# TSC_Project_v29.net
KiCad netlist of a schematic drawn in EAGLE
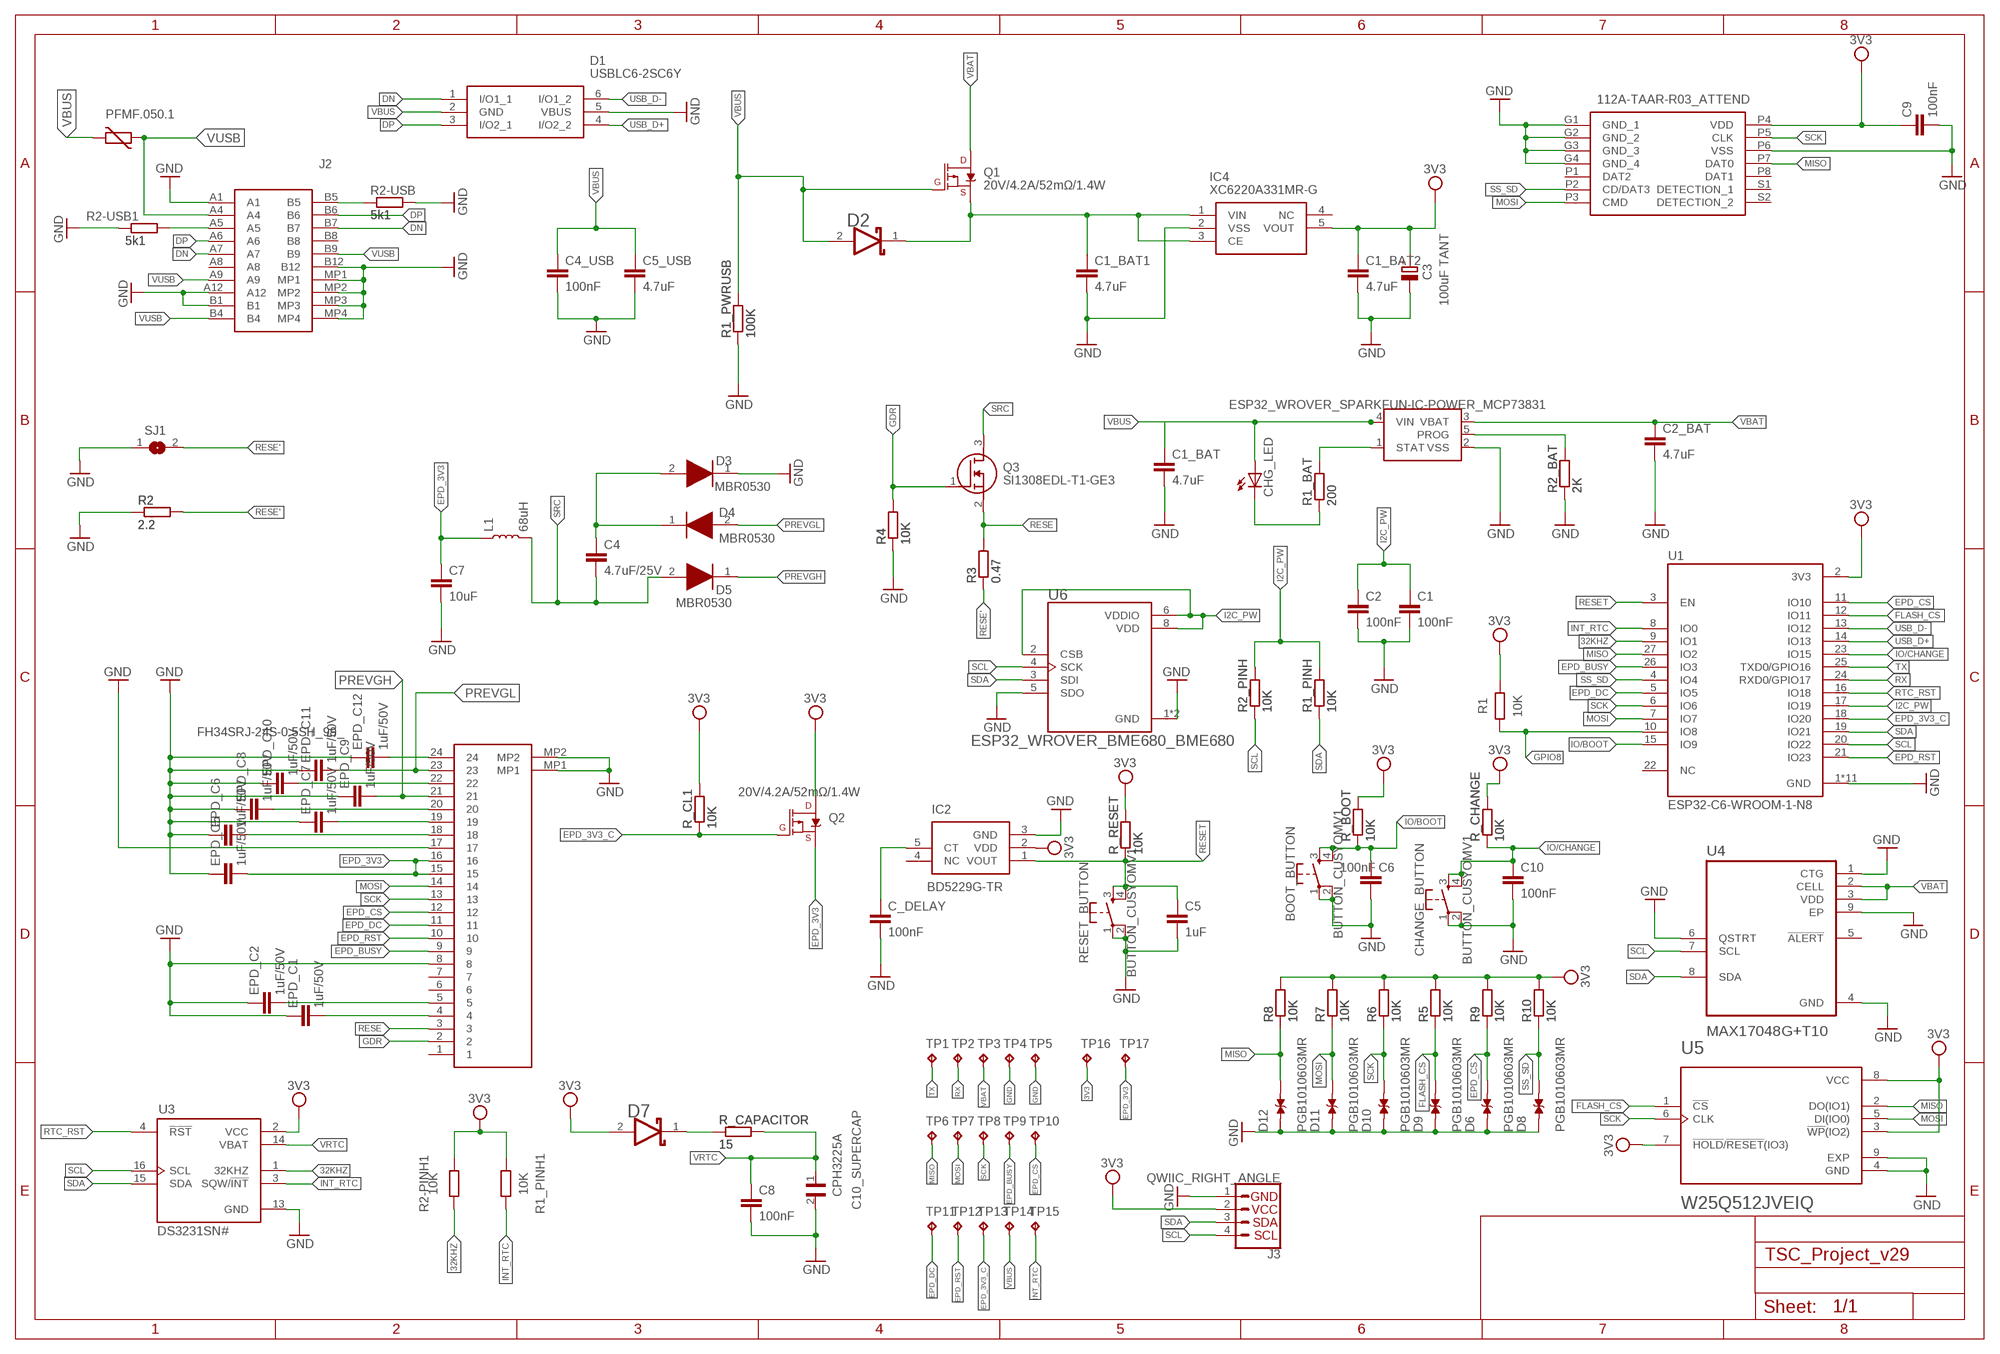
[diagram p0: schematic, sheet 1]

(export (version "E")
  (design (tool "Eeschema 10.0.6"))
  (components
    (comp (ref "BOOT_BUTTON")
      (value "BUTTON_CUSYOMV1")
      (footprint "eagle-import:MYBUTTON")
      (libsource (lib "eagle-import") (part "BUTTON_CUSYOMV1"))
    )
    (comp (ref "C1")
      (value "100nF")
      (footprint "eagle-import:ESP32_WROVER_EAGLE-LTSPICE_C0402")
      (libsource (lib "eagle-import") (part "ESP32_WROVER_EAGLE-LTSPICE_CC0402"))
    )
    (comp (ref "C1_BAT")
      (value "4.7uF")
      (footprint "eagle-import:ESP32_WROVER_EAGLE-LTSPICE_C0402")
      (libsource (lib "eagle-import") (part "ESP32_WROVER_EAGLE-LTSPICE_CC0402"))
    )
    (comp (ref "C1_BAT1")
      (value "4.7uF")
      (footprint "eagle-import:ESP32_WROVER_EAGLE-LTSPICE_C0402")
      (libsource (lib "eagle-import") (part "EAGLE-LTSPICE_CC0402"))
    )
    (comp (ref "C1_BAT2")
      (value "4.7uF")
      (footprint "eagle-import:ESP32_WROVER_EAGLE-LTSPICE_C0402")
      (libsource (lib "eagle-import") (part "EAGLE-LTSPICE_CC0402"))
    )
    (comp (ref "C2")
      (value "100nF")
      (footprint "eagle-import:ESP32_WROVER_EAGLE-LTSPICE_C0402")
      (libsource (lib "eagle-import") (part "ESP32_WROVER_EAGLE-LTSPICE_CC0402"))
    )
    (comp (ref "C2_BAT")
      (value "4.7uF")
      (footprint "eagle-import:ESP32_WROVER_EAGLE-LTSPICE_C0402")
      (libsource (lib "eagle-import") (part "ESP32_WROVER_EAGLE-LTSPICE_CC0402"))
    )
    (comp (ref "C3")
      (value "100uF TANT")
      (footprint "eagle-import:RCL_CT3528")
      (libsource (lib "eagle-import") (part "RCL_CPOL-EUCT3528"))
    )
    (comp (ref "C4")
      (value "4.7uF/25V")
      (footprint "eagle-import:ESP32_WROVER_EAGLE-LTSPICE_C0402")
      (libsource (lib "eagle-import") (part "ESP32_WROVER_EAGLE-LTSPICE_CC0402"))
    )
    (comp (ref "C4_USB")
      (value "100nF")
      (footprint "eagle-import:ESP32_WROVER_EAGLE-LTSPICE_C0402")
      (libsource (lib "eagle-import") (part "EAGLE-LTSPICE_CC0402"))
    )
    (comp (ref "C5")
      (value "1uF")
      (footprint "eagle-import:ESP32_WROVER_EAGLE-LTSPICE_C0402")
      (libsource (lib "eagle-import") (part "ESP32_WROVER_EAGLE-LTSPICE_CC0402"))
    )
    (comp (ref "C5_USB")
      (value "4.7uF")
      (footprint "eagle-import:ESP32_WROVER_EAGLE-LTSPICE_C0402")
      (libsource (lib "eagle-import") (part "EAGLE-LTSPICE_CC0402"))
    )
    (comp (ref "C6")
      (value "100nF")
      (footprint "eagle-import:ESP32_WROVER_EAGLE-LTSPICE_C0402")
      (libsource (lib "eagle-import") (part "ESP32_WROVER_EAGLE-LTSPICE_CC0402"))
    )
    (comp (ref "C7")
      (value "10uF")
      (footprint "eagle-import:ESP32_WROVER_EAGLE-LTSPICE_C0402")
      (libsource (lib "eagle-import") (part "ESP32_WROVER_EAGLE-LTSPICE_CC0402"))
    )
    (comp (ref "C8")
      (value "100nF")
      (footprint "eagle-import:ESP32_WROVER_EAGLE-LTSPICE_C0402")
      (libsource (lib "eagle-import") (part "ESP32_WROVER_EAGLE-LTSPICE_CC0402"))
    )
    (comp (ref "C9")
      (value "100nF")
      (footprint "eagle-import:ESP32_WROVER_EAGLE-LTSPICE_C0402")
      (libsource (lib "eagle-import") (part "ESP32_WROVER_EAGLE-LTSPICE_CC0402"))
    )
    (comp (ref "C10")
      (value "100nF")
      (footprint "eagle-import:ESP32_WROVER_EAGLE-LTSPICE_C0402")
      (libsource (lib "eagle-import") (part "ESP32_WROVER_EAGLE-LTSPICE_CC0402"))
    )
    (comp (ref "C10_SUPERCAP")
      (value "CPH3225A")
      (footprint "eagle-import:CAPCP3225X100N")
      (fields (field (name "MF") "Seiko Instruments"))
      (libsource (lib "eagle-import") (part "CPH3225A"))
    )
    (comp (ref "CHANGE_BUTTON")
      (value "BUTTON_CUSYOMV1")
      (footprint "eagle-import:MYBUTTON")
      (libsource (lib "eagle-import") (part "BUTTON_CUSYOMV1"))
    )
    (comp (ref "CHG_LED")
      (value "ADAFRUIT_LEDCHIP-LED0603")
      (footprint "eagle-import:ADAFRUIT_CHIP-LED0603")
      (libsource (lib "eagle-import") (part "ADAFRUIT_LEDCHIP-LED0603"))
    )
    (comp (ref "C_DELAY")
      (value "100nF")
      (footprint "eagle-import:ESP32_WROVER_EAGLE-LTSPICE_C0402")
      (libsource (lib "eagle-import") (part "EAGLE-LTSPICE_CC0402"))
    )
    (comp (ref "D1")
      (value "USBLC6-2SC6Y")
      (footprint "eagle-import:SOT95P280X145-6N")
      (fields (field (name "MF") "STMicroelectronics"))
      (libsource (lib "eagle-import") (part "USBLC6-2SC6Y"))
    )
    (comp (ref "D2")
      (value "ESP32_WROVER_AVX---SD0805S020S1R0_AVX_SD0805S020S1R0_0_0AVX_SD0805S020S1R0_0_0")
      (footprint "eagle-import:ESP32_WROVER_AVX---SD0805S020S1R0_AVX_SD0805S020S1R0_0")
      (fields
        (field (name "DIGIKEY_PART_NUMBER") "478-7800-1-ND")
        (field (name "MF") "AVX")
        (field (name "MOUSER_PART_NUMBER") "581-SD0805S020S1R0")
      )
      (libsource (lib "eagle-import") (part "ESP32_WROVER_AVX---SD0805S020S1R0_AVX_SD0805S020S1R0_0_0AVX_SD0805S020S1R0_0_0"))
    )
    (comp (ref "D3")
      (value "MBR0530")
      (footprint "eagle-import:SOD3716X135N")
      (fields (field (name "MF") "ON Semiconductor"))
      (libsource (lib "eagle-import") (part "MBR0530"))
    )
    (comp (ref "D4")
      (value "MBR0530")
      (footprint "eagle-import:SOD3716X135N")
      (fields (field (name "MF") "ON Semiconductor"))
      (libsource (lib "eagle-import") (part "MBR0530"))
    )
    (comp (ref "D5")
      (value "MBR0530")
      (footprint "eagle-import:SOD3716X135N")
      (fields (field (name "MF") "ON Semiconductor"))
      (libsource (lib "eagle-import") (part "MBR0530"))
    )
    (comp (ref "D6")
      (value "PGB1010603MR")
      (footprint "eagle-import:DIOC1608X36N")
      (fields (field (name "MF") "Littelfuse Inc."))
      (libsource (lib "eagle-import") (part "PGB1010603MR"))
    )
    (comp (ref "D7")
      (value "ESP32_WROVER_AVX---SD0805S020S1R0_AVX_SD0805S020S1R0_0_0AVX_SD0805S020S1R0_0_0")
      (footprint "eagle-import:ESP32_WROVER_AVX---SD0805S020S1R0_AVX_SD0805S020S1R0_0")
      (fields
        (field (name "DIGIKEY_PART_NUMBER") "478-7800-1-ND")
        (field (name "MF") "AVX")
        (field (name "MOUSER_PART_NUMBER") "581-SD0805S020S1R0")
      )
      (libsource (lib "eagle-import") (part "ESP32_WROVER_AVX---SD0805S020S1R0_AVX_SD0805S020S1R0_0_0AVX_SD0805S020S1R0_0_0"))
    )
    (comp (ref "D8")
      (value "PGB1010603MR")
      (footprint "eagle-import:DIOC1608X36N")
      (fields (field (name "MF") "Littelfuse Inc."))
      (libsource (lib "eagle-import") (part "PGB1010603MR"))
    )
    (comp (ref "D9")
      (value "PGB1010603MR")
      (footprint "eagle-import:DIOC1608X36N")
      (fields (field (name "MF") "Littelfuse Inc."))
      (libsource (lib "eagle-import") (part "PGB1010603MR"))
    )
    (comp (ref "D10")
      (value "PGB1010603MR")
      (footprint "eagle-import:DIOC1608X36N")
      (fields (field (name "MF") "Littelfuse Inc."))
      (libsource (lib "eagle-import") (part "PGB1010603MR"))
    )
    (comp (ref "D11")
      (value "PGB1010603MR")
      (footprint "eagle-import:DIOC1608X36N")
      (fields (field (name "MF") "Littelfuse Inc."))
      (libsource (lib "eagle-import") (part "PGB1010603MR"))
    )
    (comp (ref "D12")
      (value "PGB1010603MR")
      (footprint "eagle-import:DIOC1608X36N")
      (fields (field (name "MF") "Littelfuse Inc."))
      (libsource (lib "eagle-import") (part "PGB1010603MR"))
    )
    (comp (ref "EPD_C1")
      (value "1uF/50V")
      (footprint "eagle-import:ESP32_WROVER_EAGLE-LTSPICE_C0402")
      (libsource (lib "eagle-import") (part "ESP32_WROVER_EAGLE-LTSPICE_CC0402"))
    )
    (comp (ref "EPD_C2")
      (value "1uF/50V")
      (footprint "eagle-import:ESP32_WROVER_EAGLE-LTSPICE_C0402")
      (libsource (lib "eagle-import") (part "ESP32_WROVER_EAGLE-LTSPICE_CC0402"))
    )
    (comp (ref "EPD_C5")
      (value "1uF/50V")
      (footprint "eagle-import:ESP32_WROVER_EAGLE-LTSPICE_C0402")
      (libsource (lib "eagle-import") (part "ESP32_WROVER_EAGLE-LTSPICE_CC0402"))
    )
    (comp (ref "EPD_C6")
      (value "1uF/50V")
      (footprint "eagle-import:ESP32_WROVER_EAGLE-LTSPICE_C0402")
      (libsource (lib "eagle-import") (part "ESP32_WROVER_EAGLE-LTSPICE_CC0402"))
    )
    (comp (ref "EPD_C7")
      (value "1uF/50V")
      (footprint "eagle-import:ESP32_WROVER_EAGLE-LTSPICE_C0402")
      (libsource (lib "eagle-import") (part "ESP32_WROVER_EAGLE-LTSPICE_CC0402"))
    )
    (comp (ref "EPD_C8")
      (value "1uF/50V")
      (footprint "eagle-import:ESP32_WROVER_EAGLE-LTSPICE_C0402")
      (libsource (lib "eagle-import") (part "ESP32_WROVER_EAGLE-LTSPICE_CC0402"))
    )
    (comp (ref "EPD_C9")
      (value "1uF/50V")
      (footprint "eagle-import:ESP32_WROVER_EAGLE-LTSPICE_C0402")
      (libsource (lib "eagle-import") (part "ESP32_WROVER_EAGLE-LTSPICE_CC0402"))
    )
    (comp (ref "EPD_C10")
      (value "1uF/50V")
      (footprint "eagle-import:ESP32_WROVER_EAGLE-LTSPICE_C0402")
      (libsource (lib "eagle-import") (part "ESP32_WROVER_EAGLE-LTSPICE_CC0402"))
    )
    (comp (ref "EPD_C11")
      (value "1uF/50V")
      (footprint "eagle-import:ESP32_WROVER_EAGLE-LTSPICE_C0402")
      (libsource (lib "eagle-import") (part "ESP32_WROVER_EAGLE-LTSPICE_CC0402"))
    )
    (comp (ref "EPD_C12")
      (value "1uF/50V")
      (footprint "eagle-import:ESP32_WROVER_EAGLE-LTSPICE_C0402")
      (libsource (lib "eagle-import") (part "ESP32_WROVER_EAGLE-LTSPICE_CC0402"))
    )
    (comp (ref "IC2")
      (value "BD5229G-TR")
      (footprint "eagle-import:SOT95P280X125-5N")
      (fields (field (name "MOUSER_PART_NUMBER") "755-BD5229G-TR"))
      (libsource (lib "eagle-import") (part "BD5229G-TR"))
    )
    (comp (ref "IC4")
      (value "XC6220A331MR-G")
      (footprint "eagle-import:SOT95P280X120-5N")
      (fields (field (name "MOUSER_PART_NUMBER") "865-XC6220A331MR-G"))
      (libsource (lib "eagle-import") (part "XC6220A331MR-G"))
    )
    (comp (ref "J1")
      (value "FH34SRJ-24S-0.5SH_99_")
      (footprint "eagle-import:FH34SRJ24S05SH99")
      (fields
        (field (name "MANUFACTURER_PART_NUMBER") "FH34SRJ-24S-0.5SH(99)")
        (field (name "MOUSER_PART_NUMBER") "798-FH34SRJ24S05SH99")
      )
      (libsource (lib "eagle-import") (part "FH34SRJ-24S-0.5SH_99_"))
    )
    (comp (ref "J2")
      (value "SAMACSYS_PARTS_USB4110-GF-A")
      (footprint "eagle-import:SAMACSYS_PARTS_USB4110GFA")
      (fields
        (field (name "MANUFACTURER_PART_NUMBER") "USB4110-GF-A")
        (field (name "MOUSER_PART_NUMBER") "640-USB4110-GF-A")
      )
      (libsource (lib "eagle-import") (part "SAMACSYS_PARTS_USB4110-GF-A"))
    )
    (comp (ref "J3")
      (value "QWIIC_RIGHT_ANGLE")
      (footprint "eagle-import:JST04_1MM_RA")
      (libsource (lib "eagle-import") (part "QWIIC_CONNECTORJS-1MM"))
    )
    (comp (ref "J4")
      (value "112A-TAAR-R03_ATTEND")
      (footprint "eagle-import:112ATAARR03ATTEND")
      (fields (field (name "MANUFACTURER_PART_NUMBER") "112A-TAAR-R03 ATTEND"))
      (libsource (lib "eagle-import") (part "112A-TAAR-R03_ATTEND"))
    )
    (comp (ref "L1")
      (value "68uH")
      (footprint "eagle-import:CR75")
      (libsource (lib "eagle-import") (part "INDUCTOR-CR75-68UH"))
    )
    (comp (ref "PFMF.050.1")
      (value "ESP32C6_VARISTORCN1812")
      (footprint "eagle-import:ESP32C6_VARISTOR_CT_CN1812")
      (libsource (lib "eagle-import") (part "ESP32C6_VARISTORCN1812"))
    )
    (comp (ref "Q1")
      (value "20V/4.2A/52mΩ/1.4W")
      (footprint "eagle-import:ESP32_WROVER_SPARKFUN-DISCRETESEMI_SOT23-3")
      (libsource (lib "eagle-import") (part "ESP32_WROVER_SPARKFUN-DISCRETESEMI_MOSFET_PCH-DMG2305UX-7"))
    )
    (comp (ref "Q2")
      (value "20V/4.2A/52mΩ/1.4W")
      (footprint "eagle-import:ESP32_WROVER_SPARKFUN-DISCRETESEMI_SOT23-3")
      (libsource (lib "eagle-import") (part "ESP32_WROVER_SPARKFUN-DISCRETESEMI_MOSFET_PCH-DMG2305UX-7"))
    )
    (comp (ref "Q3")
      (value "SI1308EDL-T1-GE3")
      (footprint "eagle-import:SOT65P210X110-3N")
      (fields (field (name "MF") "Vishay Siliconix"))
      (libsource (lib "eagle-import") (part "SI1308EDL-T1-GE3"))
    )
    (comp (ref "R1")
      (value "10K")
      (footprint "eagle-import:ESP32_WROVER_EAGLE-LTSPICE_R0402")
      (libsource (lib "eagle-import") (part "ESP32_WROVER_EAGLE-LTSPICE_RR0402"))
    )
    (comp (ref "R1_BAT")
      (value "200")
      (footprint "eagle-import:ESP32_WROVER_EAGLE-LTSPICE_R0402")
      (libsource (lib "eagle-import") (part "ESP32_WROVER_EAGLE-LTSPICE_RR0402"))
    )
    (comp (ref "R1_PINH")
      (value "10K")
      (footprint "eagle-import:ESP32_WROVER_EAGLE-LTSPICE_R0402")
      (libsource (lib "eagle-import") (part "ESP32_WROVER_EAGLE-LTSPICE_RR0402"))
    )
    (comp (ref "R1_PINH1")
      (value "10K")
      (footprint "eagle-import:ESP32_WROVER_EAGLE-LTSPICE_R0402")
      (libsource (lib "eagle-import") (part "ESP32_WROVER_EAGLE-LTSPICE_RR0402"))
    )
    (comp (ref "R1_PWRUSB")
      (value "100K")
      (footprint "eagle-import:ESP32_WROVER_EAGLE-LTSPICE_R0402")
      (libsource (lib "eagle-import") (part "ESP32_WROVER_EAGLE-LTSPICE_RR0402"))
    )
    (comp (ref "R2")
      (value "2.2")
      (footprint "eagle-import:ESP32_WROVER_EAGLE-LTSPICE_R0402")
      (libsource (lib "eagle-import") (part "ESP32_WROVER_EAGLE-LTSPICE_RR0402"))
    )
    (comp (ref "R2-PINH1")
      (value "10K")
      (footprint "eagle-import:ESP32_WROVER_EAGLE-LTSPICE_R0402")
      (libsource (lib "eagle-import") (part "ESP32_WROVER_EAGLE-LTSPICE_RR0402"))
    )
    (comp (ref "R2-USB")
      (value "5k1")
      (footprint "eagle-import:ESP32_WROVER_EAGLE-LTSPICE_R0402")
      (libsource (lib "eagle-import") (part "ESP32_WROVER_EAGLE-LTSPICE_RR0402"))
    )
    (comp (ref "R2-USB1")
      (value "5k1")
      (footprint "eagle-import:ESP32_WROVER_EAGLE-LTSPICE_R0402")
      (libsource (lib "eagle-import") (part "ESP32_WROVER_EAGLE-LTSPICE_RR0402"))
    )
    (comp (ref "R2_BAT")
      (value "2K")
      (footprint "eagle-import:ESP32_WROVER_EAGLE-LTSPICE_R0402")
      (libsource (lib "eagle-import") (part "ESP32_WROVER_EAGLE-LTSPICE_RR0402"))
    )
    (comp (ref "R2_PINH")
      (value "10K")
      (footprint "eagle-import:ESP32_WROVER_EAGLE-LTSPICE_R0402")
      (libsource (lib "eagle-import") (part "ESP32_WROVER_EAGLE-LTSPICE_RR0402"))
    )
    (comp (ref "R3")
      (value "0.47")
      (footprint "eagle-import:ESP32_WROVER_EAGLE-LTSPICE_R0402")
      (libsource (lib "eagle-import") (part "ESP32_WROVER_EAGLE-LTSPICE_RR0402"))
    )
    (comp (ref "R4")
      (value "10K")
      (footprint "eagle-import:ESP32_WROVER_EAGLE-LTSPICE_R0402")
      (libsource (lib "eagle-import") (part "ESP32_WROVER_EAGLE-LTSPICE_RR0402"))
    )
    (comp (ref "R5")
      (value "10K")
      (footprint "eagle-import:ESP32_WROVER_EAGLE-LTSPICE_R0402")
      (libsource (lib "eagle-import") (part "ESP32_WROVER_EAGLE-LTSPICE_RR0402"))
    )
    (comp (ref "R6")
      (value "10K")
      (footprint "eagle-import:ESP32_WROVER_EAGLE-LTSPICE_R0402")
      (libsource (lib "eagle-import") (part "ESP32_WROVER_EAGLE-LTSPICE_RR0402"))
    )
    (comp (ref "R7")
      (value "10K")
      (footprint "eagle-import:ESP32_WROVER_EAGLE-LTSPICE_R0402")
      (libsource (lib "eagle-import") (part "ESP32_WROVER_EAGLE-LTSPICE_RR0402"))
    )
    (comp (ref "R8")
      (value "10K")
      (footprint "eagle-import:ESP32_WROVER_EAGLE-LTSPICE_R0402")
      (libsource (lib "eagle-import") (part "ESP32_WROVER_EAGLE-LTSPICE_RR0402"))
    )
    (comp (ref "R9")
      (value "10K")
      (footprint "eagle-import:ESP32_WROVER_EAGLE-LTSPICE_R0402")
      (libsource (lib "eagle-import") (part "ESP32_WROVER_EAGLE-LTSPICE_RR0402"))
    )
    (comp (ref "R10")
      (value "10K")
      (footprint "eagle-import:ESP32_WROVER_EAGLE-LTSPICE_R0402")
      (libsource (lib "eagle-import") (part "ESP32_WROVER_EAGLE-LTSPICE_RR0402"))
    )
    (comp (ref "RESET_BUTTON")
      (value "BUTTON_CUSYOMV1")
      (footprint "eagle-import:MYBUTTON")
      (libsource (lib "eagle-import") (part "BUTTON_CUSYOMV1"))
    )
    (comp (ref "R_BOOT")
      (value "10K")
      (footprint "eagle-import:ESP32_WROVER_EAGLE-LTSPICE_R0402")
      (libsource (lib "eagle-import") (part "ESP32_WROVER_EAGLE-LTSPICE_RR0402"))
    )
    (comp (ref "R_CAPACITOR")
      (value "15")
      (footprint "eagle-import:ESP32_WROVER_EAGLE-LTSPICE_R0402")
      (libsource (lib "eagle-import") (part "ESP32_WROVER_EAGLE-LTSPICE_RR0402"))
    )
    (comp (ref "R_CHANGE")
      (value "10K")
      (footprint "eagle-import:ESP32_WROVER_EAGLE-LTSPICE_R0402")
      (libsource (lib "eagle-import") (part "ESP32_WROVER_EAGLE-LTSPICE_RR0402"))
    )
    (comp (ref "R_CL1")
      (value "10K")
      (footprint "eagle-import:ESP32_WROVER_EAGLE-LTSPICE_R0402")
      (libsource (lib "eagle-import") (part "ESP32_WROVER_EAGLE-LTSPICE_RR0402"))
    )
    (comp (ref "R_RESET")
      (value "10K")
      (footprint "eagle-import:ESP32_WROVER_EAGLE-LTSPICE_R0402")
      (libsource (lib "eagle-import") (part "ESP32_WROVER_EAGLE-LTSPICE_RR0402"))
    )
    (comp (ref "SJ1") (value "SJ") (footprint "eagle-import:SJ") (libsource (lib "eagle-import") (part "SJ")))
    (comp (ref "TP1")
      (value "TPTP20R")
      (footprint "eagle-import:TP20R")
      (libsource (lib "eagle-import") (part "TPTP20R"))
    )
    (comp (ref "TP2")
      (value "TPTP20R")
      (footprint "eagle-import:TP20R")
      (libsource (lib "eagle-import") (part "TPTP20R"))
    )
    (comp (ref "TP3")
      (value "TPTP20R")
      (footprint "eagle-import:TP20R")
      (libsource (lib "eagle-import") (part "TPTP20R"))
    )
    (comp (ref "TP4")
      (value "TPTP20R")
      (footprint "eagle-import:TP20R")
      (libsource (lib "eagle-import") (part "TPTP20R"))
    )
    (comp (ref "TP5")
      (value "TPTP20R")
      (footprint "eagle-import:TP20R")
      (libsource (lib "eagle-import") (part "TPTP20R"))
    )
    (comp (ref "TP6")
      (value "TPTP20R")
      (footprint "eagle-import:TP20R")
      (libsource (lib "eagle-import") (part "TPTP20R"))
    )
    (comp (ref "TP7")
      (value "TPTP20R")
      (footprint "eagle-import:TP20R")
      (libsource (lib "eagle-import") (part "TPTP20R"))
    )
    (comp (ref "TP8")
      (value "TPTP20R")
      (footprint "eagle-import:TP20R")
      (libsource (lib "eagle-import") (part "TPTP20R"))
    )
    (comp (ref "TP9")
      (value "TPTP20R")
      (footprint "eagle-import:TP20R")
      (libsource (lib "eagle-import") (part "TPTP20R"))
    )
    (comp (ref "TP10")
      (value "TPTP20R")
      (footprint "eagle-import:TP20R")
      (libsource (lib "eagle-import") (part "TPTP20R"))
    )
    (comp (ref "TP11")
      (value "TPTP20R")
      (footprint "eagle-import:TP20R")
      (libsource (lib "eagle-import") (part "TPTP20R"))
    )
    (comp (ref "TP12")
      (value "TPTP20R")
      (footprint "eagle-import:TP20R")
      (libsource (lib "eagle-import") (part "TPTP20R"))
    )
    (comp (ref "TP13")
      (value "TPTP20R")
      (footprint "eagle-import:TP20R")
      (libsource (lib "eagle-import") (part "TPTP20R"))
    )
    (comp (ref "TP14")
      (value "TPTP20R")
      (footprint "eagle-import:TP20R")
      (libsource (lib "eagle-import") (part "TPTP20R"))
    )
    (comp (ref "TP15")
      (value "TPTP20R")
      (footprint "eagle-import:TP20R")
      (libsource (lib "eagle-import") (part "TPTP20R"))
    )
    (comp (ref "TP16")
      (value "TPTP20R")
      (footprint "eagle-import:TP20R")
      (libsource (lib "eagle-import") (part "TPTP20R"))
    )
    (comp (ref "TP17")
      (value "TPTP20R")
      (footprint "eagle-import:TP20R")
      (libsource (lib "eagle-import") (part "TPTP20R"))
    )
    (comp (ref "U1")
      (value "ESP32-C6-WROOM-1-N8")
      (footprint "eagle-import:XCVR_ESP32-C6-WROOM-1-N8")
      (fields (field (name "MF") "Espressif Systems"))
      (libsource (lib "eagle-import") (part "ESP32-C6-WROOM-1-N8"))
    )
    (comp (ref "U2")
      (value "ESP32_WROVER_SPARKFUN-IC-POWER_MCP73831")
      (footprint "eagle-import:ESP32_WROVER_SPARKFUN-IC-POWER_SOT23-5")
      (libsource (lib "eagle-import") (part "ESP32_WROVER_SPARKFUN-IC-POWER_MCP73831"))
    )
    (comp (ref "U3")
      (value "DS3231SN#")
      (footprint "eagle-import:SOIC127P1032X265-16N")
      (fields (field (name "MF") "Analog Devices"))
      (libsource (lib "eagle-import") (part "DS3231SN#"))
    )
    (comp (ref "U4")
      (value "MAX17048G+T10")
      (footprint "eagle-import:SON50P200X200X80-9N")
      (fields (field (name "MF") "Analog Devices"))
      (libsource (lib "eagle-import") (part "MAX17048G+T10"))
    )
    (comp (ref "U5")
      (value "W25Q512JVEIQ")
      (footprint "eagle-import:SON127P600X800X80-9N")
      (fields (field (name "MF") "Winbond Electronics"))
      (libsource (lib "eagle-import") (part "W25Q512JVEIQ"))
    )
    (comp (ref "U6")
      (value "ESP32_WROVER_BME680_BME680")
      (footprint "eagle-import:ESP32_WROVER_BME680_PSON80P300X300X100-8N")
      (fields (field (name "MF") "Bosch Sensortec") (field (name "MP") "BME680"))
      (libsource (lib "eagle-import") (part "ESP32_WROVER_BME680_BME680"))
    )
  )
  (nets
    (net (code "1") (name "3V3") (class "Default")
      (node (ref "C1_BAT2") (pin "1") (pinfunction "1_1") (pintype "passive"))
      (node (ref "C3") (pin "+") (pinfunction "+_+") (pintype "passive"))
      (node (ref "C9") (pin "1") (pinfunction "1_1") (pintype "passive"))
      (node (ref "D7") (pin "2") (pinfunction "ANODE_2") (pintype "bidirectional"))
      (node (ref "IC2") (pin "2") (pinfunction "VDD_2") (pintype "bidirectional"))
      (node (ref "IC4") (pin "5") (pinfunction "VOUT_5") (pintype "bidirectional"))
      (node (ref "J3") (pin "2") (pinfunction "2_2") (pintype "power_in"))
      (node (ref "J4") (pin "P4") (pinfunction "VDD_P4") (pintype "bidirectional"))
      (node (ref "Q2") (pin "3") (pinfunction "D_3") (pintype "bidirectional"))
      (node (ref "R1") (pin "2") (pinfunction "2_2") (pintype "passive"))
      (node (ref "R10") (pin "2") (pinfunction "2_2") (pintype "passive"))
      (node (ref "R1_PINH1") (pin "2") (pinfunction "2_2") (pintype "passive"))
      (node (ref "R2-PINH1") (pin "2") (pinfunction "2_2") (pintype "passive"))
      (node (ref "R5") (pin "2") (pinfunction "2_2") (pintype "passive"))
      (node (ref "R6") (pin "2") (pinfunction "2_2") (pintype "passive"))
      (node (ref "R7") (pin "2") (pinfunction "2_2") (pintype "passive"))
      (node (ref "R8") (pin "2") (pinfunction "2_2") (pintype "passive"))
      (node (ref "R9") (pin "2") (pinfunction "2_2") (pintype "passive"))
      (node (ref "R_BOOT") (pin "2") (pinfunction "2_2") (pintype "passive"))
      (node (ref "R_CHANGE") (pin "2") (pinfunction "2_2") (pintype "passive"))
      (node (ref "R_CL1") (pin "2") (pinfunction "2_2") (pintype "passive"))
      (node (ref "R_RESET") (pin "2") (pinfunction "2_2") (pintype "passive"))
      (node (ref "TP16") (pin "TP") (pinfunction "TP_TP") (pintype "input"))
      (node (ref "U1") (pin "2") (pinfunction "3V3_2") (pintype "power_in"))
      (node (ref "U3") (pin "2") (pinfunction "VCC_2") (pintype "power_in"))
      (node (ref "U5") (pin "3") (pinfunction "~{WP}(IO2)_3") (pintype "bidirectional"))
      (node (ref "U5") (pin "7") (pinfunction "~{HOLD}/~{RESET}(IO3)_7") (pintype "bidirectional"))
      (node (ref "U5") (pin "8") (pinfunction "VCC_8") (pintype "power_in"))
    )
    (net (code "2") (name "32KHZ") (class "Default")
      (node (ref "R2-PINH1") (pin "1") (pinfunction "1_1") (pintype "passive"))
      (node (ref "U1") (pin "9") (pinfunction "IO1_9") (pintype "bidirectional"))
      (node (ref "U3") (pin "1") (pinfunction "32KHZ_1") (pintype "output"))
    )
    (net (code "3") (name "DN") (class "Default")
      (node (ref "D1") (pin "1") (pinfunction "I/O1_1_1") (pintype "bidirectional"))
      (node (ref "J2") (pin "A7") (pinfunction "A7_A7") (pintype "bidirectional"))
      (node (ref "J2") (pin "B7") (pinfunction "B7_B7") (pintype "bidirectional"))
    )
    (net (code "4") (name "DP") (class "Default")
      (node (ref "D1") (pin "3") (pinfunction "I/O2_1_3") (pintype "bidirectional"))
      (node (ref "J2") (pin "A6") (pinfunction "A6_A6") (pintype "bidirectional"))
      (node (ref "J2") (pin "B6") (pinfunction "B6_B6") (pintype "bidirectional"))
    )
    (net (code "5") (name "EPD_3V3") (class "Default")
      (node (ref "C7") (pin "1") (pinfunction "1_1") (pintype "passive"))
      (node (ref "EPD_C5") (pin "2") (pinfunction "2_2") (pintype "passive"))
      (node (ref "J1") (pin "15") (pinfunction "15_15") (pintype "bidirectional"))
      (node (ref "J1") (pin "16") (pinfunction "16_16") (pintype "bidirectional"))
      (node (ref "L1") (pin "P$1") (pinfunction "1_P$1") (pintype "passive"))
      (node (ref "Q2") (pin "2") (pinfunction "S_2") (pintype "bidirectional"))
      (node (ref "TP17") (pin "TP") (pinfunction "TP_TP") (pintype "input"))
    )
    (net (code "6") (name "EPD_3V3_C") (class "Default")
      (node (ref "Q2") (pin "1") (pinfunction "G_1") (pintype "bidirectional"))
      (node (ref "R_CL1") (pin "1") (pinfunction "1_1") (pintype "passive"))
      (node (ref "TP13") (pin "TP") (pinfunction "TP_TP") (pintype "input"))
      (node (ref "U1") (pin "18") (pinfunction "IO20_18") (pintype "bidirectional"))
    )
    (net (code "7") (name "EPD_BUSY") (class "Default")
      (node (ref "J1") (pin "9") (pinfunction "9_9") (pintype "bidirectional"))
      (node (ref "TP9") (pin "TP") (pinfunction "TP_TP") (pintype "input"))
      (node (ref "U1") (pin "26") (pinfunction "IO3_26") (pintype "bidirectional"))
    )
    (net (code "8") (name "EPD_CS") (class "Default")
      (node (ref "D6") (pin "2") (pinfunction "2_2") (pintype "passive"))
      (node (ref "J1") (pin "12") (pinfunction "12_12") (pintype "bidirectional"))
      (node (ref "R9") (pin "1") (pinfunction "1_1") (pintype "passive"))
      (node (ref "TP10") (pin "TP") (pinfunction "TP_TP") (pintype "input"))
      (node (ref "U1") (pin "11") (pinfunction "IO10_11") (pintype "bidirectional"))
    )
    (net (code "9") (name "EPD_DC") (class "Default")
      (node (ref "J1") (pin "11") (pinfunction "11_11") (pintype "bidirectional"))
      (node (ref "TP11") (pin "TP") (pinfunction "TP_TP") (pintype "input"))
      (node (ref "U1") (pin "5") (pinfunction "IO5_5") (pintype "bidirectional"))
    )
    (net (code "10") (name "EPD_RST") (class "Default")
      (node (ref "J1") (pin "10") (pinfunction "10_10") (pintype "bidirectional"))
      (node (ref "TP12") (pin "TP") (pinfunction "TP_TP") (pintype "input"))
      (node (ref "U1") (pin "21") (pinfunction "IO23_21") (pintype "bidirectional"))
    )
    (net (code "11") (name "FLASH_CS") (class "Default")
      (node (ref "D9") (pin "2") (pinfunction "2_2") (pintype "passive"))
      (node (ref "R5") (pin "1") (pinfunction "1_1") (pintype "passive"))
      (node (ref "U1") (pin "12") (pinfunction "IO11_12") (pintype "bidirectional"))
      (node (ref "U5") (pin "1") (pinfunction "~{CS}_1") (pintype "input"))
    )
    (net (code "12") (name "GDR") (class "Default")
      (node (ref "J1") (pin "2") (pinfunction "2_2") (pintype "bidirectional"))
      (node (ref "Q3") (pin "1") (pinfunction "G_1") (pintype "bidirectional"))
      (node (ref "R4") (pin "2") (pinfunction "2_2") (pintype "passive"))
    )
    (net (code "13") (name "GND") (class "Default")
      (node (ref "BOOT_BUTTON") (pin "1") (pinfunction "1_1") (pintype "passive"))
      (node (ref "BOOT_BUTTON") (pin "2") (pinfunction "2_2") (pintype "passive"))
      (node (ref "C1") (pin "2") (pinfunction "2_2") (pintype "passive"))
      (node (ref "C10") (pin "2") (pinfunction "2_2") (pintype "passive"))
      (node (ref "C10_SUPERCAP") (pin "2") (pinfunction "2_2") (pintype "passive"))
      (node (ref "C1_BAT") (pin "2") (pinfunction "2_2") (pintype "passive"))
      (node (ref "C1_BAT1") (pin "2") (pinfunction "2_2") (pintype "passive"))
      (node (ref "C1_BAT2") (pin "2") (pinfunction "2_2") (pintype "passive"))
      (node (ref "C2") (pin "2") (pinfunction "2_2") (pintype "passive"))
      (node (ref "C2_BAT") (pin "2") (pinfunction "2_2") (pintype "passive"))
      (node (ref "C3") (pin "-") (pinfunction "-_-") (pintype "passive"))
      (node (ref "C4_USB") (pin "2") (pinfunction "2_2") (pintype "passive"))
      (node (ref "C5") (pin "2") (pinfunction "2_2") (pintype "passive"))
      (node (ref "C5_USB") (pin "2") (pinfunction "2_2") (pintype "passive"))
      (node (ref "C6") (pin "2") (pinfunction "2_2") (pintype "passive"))
      (node (ref "C7") (pin "2") (pinfunction "2_2") (pintype "passive"))
      (node (ref "C8") (pin "2") (pinfunction "2_2") (pintype "passive"))
      (node (ref "C9") (pin "2") (pinfunction "2_2") (pintype "passive"))
      (node (ref "CHANGE_BUTTON") (pin "1") (pinfunction "1_1") (pintype "passive"))
      (node (ref "CHANGE_BUTTON") (pin "2") (pinfunction "2_2") (pintype "passive"))
      (node (ref "C_DELAY") (pin "2") (pinfunction "2_2") (pintype "passive"))
      (node (ref "D1") (pin "5") (pinfunction "VBUS_5") (pintype "bidirectional"))
      (node (ref "D10") (pin "1") (pinfunction "1_1") (pintype "passive"))
      (node (ref "D11") (pin "1") (pinfunction "1_1") (pintype "passive"))
      (node (ref "D12") (pin "1") (pinfunction "1_1") (pintype "passive"))
      (node (ref "D3") (pin "1") (pinfunction "K_1") (pintype "bidirectional"))
      (node (ref "D6") (pin "1") (pinfunction "1_1") (pintype "passive"))
      (node (ref "D8") (pin "1") (pinfunction "1_1") (pintype "passive"))
      (node (ref "D9") (pin "1") (pinfunction "1_1") (pintype "passive"))
      (node (ref "EPD_C1") (pin "1") (pinfunction "1_1") (pintype "passive"))
      (node (ref "EPD_C10") (pin "1") (pinfunction "1_1") (pintype "passive"))
      (node (ref "EPD_C11") (pin "1") (pinfunction "1_1") (pintype "passive"))
      (node (ref "EPD_C12") (pin "1") (pinfunction "1_1") (pintype "passive"))
      (node (ref "EPD_C2") (pin "1") (pinfunction "1_1") (pintype "passive"))
      (node (ref "EPD_C5") (pin "1") (pinfunction "1_1") (pintype "passive"))
      (node (ref "EPD_C6") (pin "1") (pinfunction "1_1") (pintype "passive"))
      (node (ref "EPD_C7") (pin "1") (pinfunction "1_1") (pintype "passive"))
      (node (ref "EPD_C8") (pin "1") (pinfunction "1_1") (pintype "passive"))
      (node (ref "EPD_C9") (pin "1") (pinfunction "1_1") (pintype "passive"))
      (node (ref "IC2") (pin "3") (pinfunction "GND_3") (pintype "bidirectional"))
      (node (ref "IC4") (pin "2") (pinfunction "VSS_2") (pintype "bidirectional"))
      (node (ref "J1") (pin "17") (pinfunction "17_17") (pintype "bidirectional"))
      (node (ref "J1") (pin "8") (pinfunction "8_8") (pintype "bidirectional"))
      (node (ref "J1") (pin "MP1") (pinfunction "MP1_MP1") (pintype "bidirectional"))
      (node (ref "J1") (pin "MP2") (pinfunction "MP2_MP2") (pintype "bidirectional"))
      (node (ref "J2") (pin "A1") (pinfunction "A1_A1") (pintype "bidirectional"))
      (node (ref "J2") (pin "A12") (pinfunction "A12_A12") (pintype "bidirectional"))
      (node (ref "J2") (pin "B1") (pinfunction "B1_B1") (pintype "bidirectional"))
      (node (ref "J2") (pin "B12") (pinfunction "B12_B12") (pintype "bidirectional"))
      (node (ref "J2") (pin "MP1") (pinfunction "MP1_MP1") (pintype "bidirectional"))
      (node (ref "J2") (pin "MP2") (pinfunction "MP2_MP2") (pintype "bidirectional"))
      (node (ref "J2") (pin "MP3") (pinfunction "MP3_MP3") (pintype "bidirectional"))
      (node (ref "J2") (pin "MP4") (pinfunction "MP4_MP4") (pintype "bidirectional"))
      (node (ref "J3") (pin "1") (pinfunction "1_1") (pintype "power_in"))
      (node (ref "J4") (pin "G1") (pinfunction "GND_1_G1") (pintype "bidirectional"))
      (node (ref "J4") (pin "G2") (pinfunction "GND_2_G2") (pintype "bidirectional"))
      (node (ref "J4") (pin "G3") (pinfunction "GND_3_G3") (pintype "bidirectional"))
      (node (ref "J4") (pin "G4") (pinfunction "GND_4_G4") (pintype "bidirectional"))
      (node (ref "J4") (pin "P6") (pinfunction "VSS_P6") (pintype "bidirectional"))
      (node (ref "R1_PWRUSB") (pin "1") (pinfunction "1_1") (pintype "passive"))
      (node (ref "R2") (pin "1") (pinfunction "1_1") (pintype "passive"))
      (node (ref "R2-USB") (pin "2") (pinfunction "2_2") (pintype "passive"))
      (node (ref "R2-USB1") (pin "1") (pinfunction "1_1") (pintype "passive"))
      (node (ref "R2_BAT") (pin "1") (pinfunction "1_1") (pintype "passive"))
      (node (ref "R4") (pin "1") (pinfunction "1_1") (pintype "passive"))
      (node (ref "RESET_BUTTON") (pin "1") (pinfunction "1_1") (pintype "passive"))
      (node (ref "RESET_BUTTON") (pin "2") (pinfunction "2_2") (pintype "passive"))
      (node (ref "SJ1") (pin "1") (pinfunction "1_1") (pintype "passive"))
      (node (ref "TP4") (pin "TP") (pinfunction "TP_TP") (pintype "input"))
      (node (ref "TP5") (pin "TP") (pinfunction "TP_TP") (pintype "input"))
      (node (ref "U1") (pin "1") (pinfunction "GND_1") (pintype "power_in"))
      (node (ref "U1") (pin "28") (pinfunction "GND_28") (pintype "power_in"))
      (node (ref "U1") (pin "29_1") (pinfunction "GND_29_1") (pintype "power_in"))
      (node (ref "U1") (pin "29_2") (pinfunction "GND_29_2") (pintype "power_in"))
      (node (ref "U1") (pin "29_3") (pinfunction "GND_29_3") (pintype "power_in"))
      (node (ref "U1") (pin "29_4") (pinfunction "GND_29_4") (pintype "power_in"))
      (node (ref "U1") (pin "29_5") (pinfunction "GND_29_5") (pintype "power_in"))
      (node (ref "U1") (pin "29_6") (pinfunction "GND_29_6") (pintype "power_in"))
      (node (ref "U1") (pin "29_7") (pinfunction "GND_29_7") (pintype "power_in"))
      (node (ref "U1") (pin "29_8") (pinfunction "GND_29_8") (pintype "power_in"))
      (node (ref "U1") (pin "29_9") (pinfunction "GND_29_9") (pintype "power_in"))
      (node (ref "U2") (pin "2") (pinfunction "VSS_2") (pintype "power_in"))
      (node (ref "U3") (pin "13") (pinfunction "GND_13") (pintype "power_in"))
      (node (ref "U4") (pin "1") (pinfunction "CTG_1") (pintype "power_in"))
      (node (ref "U4") (pin "4") (pinfunction "GND_4") (pintype "power_in"))
      (node (ref "U4") (pin "6") (pinfunction "QSTRT_6") (pintype "input"))
      (node (ref "U4") (pin "9") (pinfunction "EP_9") (pintype "power_in"))
      (node (ref "U5") (pin "4") (pinfunction "GND_4") (pintype "power_in"))
      (node (ref "U5") (pin "9") (pinfunction "EXP_9") (pintype "passive"))
      (node (ref "U6") (pin "1") (pinfunction "GND_1") (pintype "power_in"))
      (node (ref "U6") (pin "5") (pinfunction "SDO_5") (pintype "bidirectional"))
      (node (ref "U6") (pin "7") (pinfunction "GND_7") (pintype "power_in"))
    )
    (net (code "14") (name "GPIO8") (class "Default")
      (node (ref "R1") (pin "1") (pinfunction "1_1") (pintype "passive"))
      (node (ref "U1") (pin "10") (pinfunction "IO8_10") (pintype "bidirectional"))
    )
    (net (code "15") (name "I2C_PW") (class "Default")
      (node (ref "C1") (pin "1") (pinfunction "1_1") (pintype "passive"))
      (node (ref "C2") (pin "1") (pinfunction "1_1") (pintype "passive"))
      (node (ref "R1_PINH") (pin "2") (pinfunction "2_2") (pintype "passive"))
      (node (ref "R2_PINH") (pin "2") (pinfunction "2_2") (pintype "passive"))
      (node (ref "U1") (pin "17") (pinfunction "IO19_17") (pintype "bidirectional"))
      (node (ref "U6") (pin "2") (pinfunction "CSB_2") (pintype "input"))
      (node (ref "U6") (pin "6") (pinfunction "VDDIO_6") (pintype "power_in"))
      (node (ref "U6") (pin "8") (pinfunction "VDD_8") (pintype "power_in"))
    )
    (net (code "16") (name "INT_RTC") (class "Default")
      (node (ref "R1_PINH1") (pin "1") (pinfunction "1_1") (pintype "passive"))
      (node (ref "TP15") (pin "TP") (pinfunction "TP_TP") (pintype "input"))
      (node (ref "U1") (pin "8") (pinfunction "IO0_8") (pintype "bidirectional"))
      (node (ref "U3") (pin "3") (pinfunction "SQW/~{INT}_3") (pintype "output"))
    )
    (net (code "17") (name "IO{slash}BOOT") (class "Default")
      (node (ref "BOOT_BUTTON") (pin "3") (pinfunction "3_3") (pintype "passive"))
      (node (ref "BOOT_BUTTON") (pin "4") (pinfunction "4_4") (pintype "passive"))
      (node (ref "C6") (pin "1") (pinfunction "1_1") (pintype "passive"))
      (node (ref "R_BOOT") (pin "1") (pinfunction "1_1") (pintype "passive"))
      (node (ref "U1") (pin "15") (pinfunction "IO9_15") (pintype "bidirectional"))
    )
    (net (code "18") (name "IO{slash}CHANGE") (class "Default")
      (node (ref "C10") (pin "1") (pinfunction "1_1") (pintype "passive"))
      (node (ref "CHANGE_BUTTON") (pin "3") (pinfunction "3_3") (pintype "passive"))
      (node (ref "CHANGE_BUTTON") (pin "4") (pinfunction "4_4") (pintype "passive"))
      (node (ref "R_CHANGE") (pin "1") (pinfunction "1_1") (pintype "passive"))
      (node (ref "U1") (pin "23") (pinfunction "IO15_23") (pintype "bidirectional"))
    )
    (net (code "19") (name "MISO") (class "Default")
      (node (ref "D12") (pin "2") (pinfunction "2_2") (pintype "passive"))
      (node (ref "J4") (pin "P7") (pinfunction "DAT0_P7") (pintype "bidirectional"))
      (node (ref "R8") (pin "1") (pinfunction "1_1") (pintype "passive"))
      (node (ref "TP6") (pin "TP") (pinfunction "TP_TP") (pintype "input"))
      (node (ref "U1") (pin "27") (pinfunction "IO2_27") (pintype "bidirectional"))
      (node (ref "U5") (pin "2") (pinfunction "DO(IO1)_2") (pintype "bidirectional"))
    )
    (net (code "20") (name "MOSI") (class "Default")
      (node (ref "D11") (pin "2") (pinfunction "2_2") (pintype "passive"))
      (node (ref "J1") (pin "14") (pinfunction "14_14") (pintype "bidirectional"))
      (node (ref "J4") (pin "P3") (pinfunction "CMD_P3") (pintype "bidirectional"))
      (node (ref "R7") (pin "1") (pinfunction "1_1") (pintype "passive"))
      (node (ref "TP7") (pin "TP") (pinfunction "TP_TP") (pintype "input"))
      (node (ref "U1") (pin "7") (pinfunction "IO7_7") (pintype "bidirectional"))
      (node (ref "U5") (pin "5") (pinfunction "DI(IO0)_5") (pintype "bidirectional"))
    )
    (net (code "21") (name "Net-(CHG_LED-PadC)") (class "Default")
      (node (ref "CHG_LED") (pin "C") (pinfunction "C_C") (pintype "passive"))
      (node (ref "R1_BAT") (pin "1") (pinfunction "1_1") (pintype "passive"))
    )
    (net (code "22") (name "Net-(D2-CATHODE)") (class "Default")
      (node (ref "C1_BAT1") (pin "1") (pinfunction "1_1") (pintype "passive"))
      (node (ref "D2") (pin "1") (pinfunction "CATHODE_1") (pintype "bidirectional"))
      (node (ref "IC4") (pin "1") (pinfunction "VIN_1") (pintype "bidirectional"))
      (node (ref "IC4") (pin "3") (pinfunction "CE_3") (pintype "bidirectional"))
      (node (ref "Q1") (pin "2") (pinfunction "S_2") (pintype "bidirectional"))
    )
    (net (code "23") (name "Net-(D3-A)") (class "Default")
      (node (ref "C4") (pin "1") (pinfunction "1_1") (pintype "passive"))
      (node (ref "D3") (pin "2") (pinfunction "A_2") (pintype "bidirectional"))
      (node (ref "D4") (pin "1") (pinfunction "K_1") (pintype "bidirectional"))
    )
    (net (code "24") (name "Net-(D7-CATHODE)") (class "Default")
      (node (ref "D7") (pin "1") (pinfunction "CATHODE_1") (pintype "bidirectional"))
      (node (ref "R_CAPACITOR") (pin "1") (pinfunction "1_1") (pintype "passive"))
    )
    (net (code "25") (name "Net-(EPD_C1-Pad2)") (class "Default")
      (node (ref "EPD_C1") (pin "2") (pinfunction "2_2") (pintype "passive"))
      (node (ref "J1") (pin "4") (pinfunction "4_4") (pintype "bidirectional"))
    )
    (net (code "26") (name "Net-(EPD_C2-Pad2)") (class "Default")
      (node (ref "EPD_C2") (pin "2") (pinfunction "2_2") (pintype "passive"))
      (node (ref "J1") (pin "5") (pinfunction "5_5") (pintype "bidirectional"))
    )
    (net (code "27") (name "Net-(EPD_C6-Pad2)") (class "Default")
      (node (ref "EPD_C6") (pin "2") (pinfunction "2_2") (pintype "passive"))
      (node (ref "J1") (pin "18") (pinfunction "18_18") (pintype "bidirectional"))
    )
    (net (code "28") (name "Net-(EPD_C7-Pad2)") (class "Default")
      (node (ref "EPD_C7") (pin "2") (pinfunction "2_2") (pintype "passive"))
      (node (ref "J1") (pin "19") (pinfunction "19_19") (pintype "bidirectional"))
    )
    (net (code "29") (name "Net-(EPD_C8-Pad2)") (class "Default")
      (node (ref "EPD_C8") (pin "2") (pinfunction "2_2") (pintype "passive"))
      (node (ref "J1") (pin "20") (pinfunction "20_20") (pintype "bidirectional"))
    )
    (net (code "30") (name "Net-(EPD_C10-Pad2)") (class "Default")
      (node (ref "EPD_C10") (pin "2") (pinfunction "2_2") (pintype "passive"))
      (node (ref "J1") (pin "22") (pinfunction "22_22") (pintype "bidirectional"))
    )
    (net (code "31") (name "Net-(EPD_C12-Pad2)") (class "Default")
      (node (ref "EPD_C12") (pin "2") (pinfunction "2_2") (pintype "passive"))
      (node (ref "J1") (pin "24") (pinfunction "24_24") (pintype "bidirectional"))
    )
    (net (code "32") (name "Net-(IC2-CT)") (class "Default")
      (node (ref "C_DELAY") (pin "1") (pinfunction "1_1") (pintype "passive"))
      (node (ref "IC2") (pin "5") (pinfunction "CT_5") (pintype "bidirectional"))
    )
    (net (code "33") (name "Net-(J2-PadA5)") (class "Default")
      (node (ref "J2") (pin "A5") (pinfunction "A5_A5") (pintype "bidirectional"))
      (node (ref "R2-USB1") (pin "2") (pinfunction "2_2") (pintype "passive"))
    )
    (net (code "34") (name "Net-(J2-PadB5)") (class "Default")
      (node (ref "J2") (pin "B5") (pinfunction "B5_B5") (pintype "bidirectional"))
      (node (ref "R2-USB") (pin "1") (pinfunction "1_1") (pintype "passive"))
    )
    (net (code "35") (name "Net-(U2-PROG)") (class "Default")
      (node (ref "R2_BAT") (pin "2") (pinfunction "2_2") (pintype "passive"))
      (node (ref "U2") (pin "5") (pinfunction "PROG_5") (pintype "input"))
    )
    (net (code "36") (name "Net-(U2-STAT)") (class "Default")
      (node (ref "R1_BAT") (pin "2") (pinfunction "2_2") (pintype "passive"))
      (node (ref "U2") (pin "1") (pinfunction "STAT_1") (pintype "output"))
    )
    (net (code "37") (name "PREVGH") (class "Default")
      (node (ref "D5") (pin "1") (pinfunction "K_1") (pintype "bidirectional"))
      (node (ref "EPD_C9") (pin "2") (pinfunction "2_2") (pintype "passive"))
      (node (ref "J1") (pin "21") (pinfunction "21_21") (pintype "bidirectional"))
    )
    (net (code "38") (name "PREVGL") (class "Default")
      (node (ref "D4") (pin "2") (pinfunction "A_2") (pintype "bidirectional"))
      (node (ref "EPD_C11") (pin "2") (pinfunction "2_2") (pintype "passive"))
      (node (ref "J1") (pin "23") (pinfunction "23_23") (pintype "bidirectional"))
    )
    (net (code "39") (name "RESE") (class "Default")
      (node (ref "J1") (pin "3") (pinfunction "3_3") (pintype "bidirectional"))
      (node (ref "Q3") (pin "2") (pinfunction "S_2") (pintype "bidirectional"))
      (node (ref "R3") (pin "2") (pinfunction "2_2") (pintype "passive"))
    )
    (net (code "40") (name "RESE'") (class "Default")
      (node (ref "R2") (pin "2") (pinfunction "2_2") (pintype "passive"))
      (node (ref "R3") (pin "1") (pinfunction "1_1") (pintype "passive"))
      (node (ref "SJ1") (pin "2") (pinfunction "2_2") (pintype "passive"))
    )
    (net (code "41") (name "RESET") (class "Default")
      (node (ref "C5") (pin "1") (pinfunction "1_1") (pintype "passive"))
      (node (ref "IC2") (pin "1") (pinfunction "VOUT_1") (pintype "bidirectional"))
      (node (ref "RESET_BUTTON") (pin "3") (pinfunction "3_3") (pintype "passive"))
      (node (ref "RESET_BUTTON") (pin "4") (pinfunction "4_4") (pintype "passive"))
      (node (ref "R_RESET") (pin "1") (pinfunction "1_1") (pintype "passive"))
      (node (ref "U1") (pin "3") (pinfunction "EN_3") (pintype "input"))
    )
    (net (code "42") (name "RTC_RST") (class "Default")
      (node (ref "U1") (pin "16") (pinfunction "IO18_16") (pintype "bidirectional"))
      (node (ref "U3") (pin "4") (pinfunction "~{RST}_4") (pintype "input"))
    )
    (net (code "43") (name "RX") (class "Default")
      (node (ref "TP2") (pin "TP") (pinfunction "TP_TP") (pintype "input"))
      (node (ref "U1") (pin "24") (pinfunction "RXD0/GPIO17_24") (pintype "bidirectional"))
    )
    (net (code "44") (name "SCK") (class "Default")
      (node (ref "D10") (pin "2") (pinfunction "2_2") (pintype "passive"))
      (node (ref "J1") (pin "13") (pinfunction "13_13") (pintype "bidirectional"))
      (node (ref "J4") (pin "P5") (pinfunction "CLK_P5") (pintype "bidirectional"))
      (node (ref "R6") (pin "1") (pinfunction "1_1") (pintype "passive"))
      (node (ref "TP8") (pin "TP") (pinfunction "TP_TP") (pintype "input"))
      (node (ref "U1") (pin "6") (pinfunction "IO6_6") (pintype "bidirectional"))
      (node (ref "U5") (pin "6") (pinfunction "CLK_6") (pintype "input"))
    )
    (net (code "45") (name "SCL") (class "Default")
      (node (ref "J3") (pin "4") (pinfunction "4_4") (pintype "passive"))
      (node (ref "R2_PINH") (pin "1") (pinfunction "1_1") (pintype "passive"))
      (node (ref "U1") (pin "20") (pinfunction "IO22_20") (pintype "bidirectional"))
      (node (ref "U3") (pin "16") (pinfunction "SCL_16") (pintype "input"))
      (node (ref "U4") (pin "7") (pinfunction "SCL_7") (pintype "input"))
      (node (ref "U6") (pin "4") (pinfunction "SCK_4") (pintype "input"))
    )
    (net (code "46") (name "SDA") (class "Default")
      (node (ref "J3") (pin "3") (pinfunction "3_3") (pintype "passive"))
      (node (ref "R1_PINH") (pin "1") (pinfunction "1_1") (pintype "passive"))
      (node (ref "U1") (pin "19") (pinfunction "IO21_19") (pintype "bidirectional"))
      (node (ref "U3") (pin "15") (pinfunction "SDA_15") (pintype "bidirectional"))
      (node (ref "U4") (pin "8") (pinfunction "SDA_8") (pintype "bidirectional"))
      (node (ref "U6") (pin "3") (pinfunction "SDI_3") (pintype "bidirectional"))
    )
    (net (code "47") (name "SRC") (class "Default")
      (node (ref "C4") (pin "2") (pinfunction "2_2") (pintype "passive"))
      (node (ref "D5") (pin "2") (pinfunction "A_2") (pintype "bidirectional"))
      (node (ref "L1") (pin "P$2") (pinfunction "2_P$2") (pintype "passive"))
      (node (ref "Q3") (pin "3") (pinfunction "D_3") (pintype "bidirectional"))
    )
    (net (code "48") (name "SS_SD") (class "Default")
      (node (ref "D8") (pin "2") (pinfunction "2_2") (pintype "passive"))
      (node (ref "J4") (pin "P2") (pinfunction "CD/DAT3_P2") (pintype "bidirectional"))
      (node (ref "R10") (pin "1") (pinfunction "1_1") (pintype "passive"))
      (node (ref "U1") (pin "4") (pinfunction "IO4_4") (pintype "bidirectional"))
    )
    (net (code "49") (name "TX") (class "Default")
      (node (ref "TP1") (pin "TP") (pinfunction "TP_TP") (pintype "input"))
      (node (ref "U1") (pin "25") (pinfunction "TXD0/GPIO16_25") (pintype "bidirectional"))
    )
    (net (code "50") (name "USB_D+") (class "Default")
      (node (ref "D1") (pin "4") (pinfunction "I/O2_2_4") (pintype "bidirectional"))
      (node (ref "U1") (pin "14") (pinfunction "IO13_14") (pintype "bidirectional"))
    )
    (net (code "51") (name "USB_D-") (class "Default")
      (node (ref "D1") (pin "6") (pinfunction "I/O1_2_6") (pintype "bidirectional"))
      (node (ref "U1") (pin "13") (pinfunction "IO12_13") (pintype "bidirectional"))
    )
    (net (code "52") (name "VBAT") (class "Default")
      (node (ref "C2_BAT") (pin "1") (pinfunction "1_1") (pintype "passive"))
      (node (ref "Q1") (pin "3") (pinfunction "D_3") (pintype "bidirectional"))
      (node (ref "TP3") (pin "TP") (pinfunction "TP_TP") (pintype "input"))
      (node (ref "U2") (pin "3") (pinfunction "VBAT_3") (pintype "power_in"))
      (node (ref "U4") (pin "2") (pinfunction "CELL_2") (pintype "power_in"))
      (node (ref "U4") (pin "3") (pinfunction "VDD_3") (pintype "power_in"))
    )
    (net (code "53") (name "VBUS") (class "Default")
      (node (ref "C1_BAT") (pin "1") (pinfunction "1_1") (pintype "passive"))
      (node (ref "C4_USB") (pin "1") (pinfunction "1_1") (pintype "passive"))
      (node (ref "C5_USB") (pin "1") (pinfunction "1_1") (pintype "passive"))
      (node (ref "CHG_LED") (pin "A") (pinfunction "A_A") (pintype "passive"))
      (node (ref "D1") (pin "2") (pinfunction "GND_2") (pintype "bidirectional"))
      (node (ref "D2") (pin "2") (pinfunction "ANODE_2") (pintype "bidirectional"))
      (node (ref "PFMF.050.1") (pin "2") (pinfunction "2_2") (pintype "passive"))
      (node (ref "Q1") (pin "1") (pinfunction "G_1") (pintype "bidirectional"))
      (node (ref "R1_PWRUSB") (pin "2") (pinfunction "2_2") (pintype "passive"))
      (node (ref "TP14") (pin "TP") (pinfunction "TP_TP") (pintype "input"))
      (node (ref "U2") (pin "4") (pinfunction "VIN_4") (pintype "power_in"))
    )
    (net (code "54") (name "VRTC") (class "Default")
      (node (ref "C10_SUPERCAP") (pin "1") (pinfunction "1_1") (pintype "passive"))
      (node (ref "C8") (pin "1") (pinfunction "1_1") (pintype "passive"))
      (node (ref "R_CAPACITOR") (pin "2") (pinfunction "2_2") (pintype "passive"))
      (node (ref "U3") (pin "14") (pinfunction "VBAT_14") (pintype "power_in"))
    )
    (net (code "55") (name "VUSB") (class "Default")
      (node (ref "J2") (pin "A4") (pinfunction "A4_A4") (pintype "bidirectional"))
      (node (ref "J2") (pin "A9") (pinfunction "A9_A9") (pintype "bidirectional"))
      (node (ref "J2") (pin "B4") (pinfunction "B4_B4") (pintype "bidirectional"))
      (node (ref "J2") (pin "B9") (pinfunction "B9_B9") (pintype "bidirectional"))
      (node (ref "PFMF.050.1") (pin "1") (pinfunction "1_1") (pintype "passive"))
    )
    (net (code "56") (name "unconnected-(IC2-NC-Pad4)") (class "Default")
      (node (ref "IC2") (pin "4") (pinfunction "NC_4") (pintype "no_connect"))
    )
    (net (code "57") (name "unconnected-(IC4-NC-Pad4)") (class "Default")
      (node (ref "IC4") (pin "4") (pinfunction "NC_4") (pintype "no_connect"))
    )
    (net (code "58") (name "unconnected-(J1-Pad1)") (class "Default")
      (node (ref "J1") (pin "1") (pinfunction "1_1") (pintype "bidirectional"))
    )
    (net (code "59") (name "unconnected-(J1-Pad6)") (class "Default")
      (node (ref "J1") (pin "6") (pinfunction "6_6") (pintype "bidirectional"))
    )
    (net (code "60") (name "unconnected-(J1-Pad7)") (class "Default")
      (node (ref "J1") (pin "7") (pinfunction "7_7") (pintype "bidirectional"))
    )
    (net (code "61") (name "unconnected-(J2-PadA8)") (class "Default")
      (node (ref "J2") (pin "A8") (pinfunction "A8_A8") (pintype "bidirectional"))
    )
    (net (code "62") (name "unconnected-(J2-PadB8)") (class "Default")
      (node (ref "J2") (pin "B8") (pinfunction "B8_B8") (pintype "bidirectional"))
    )
    (net (code "63") (name "unconnected-(J4-DAT1-PadP8)") (class "Default")
      (node (ref "J4") (pin "P8") (pinfunction "DAT1_P8") (pintype "bidirectional"))
    )
    (net (code "64") (name "unconnected-(J4-DAT2-PadP1)") (class "Default")
      (node (ref "J4") (pin "P1") (pinfunction "DAT2_P1") (pintype "bidirectional"))
    )
    (net (code "65") (name "unconnected-(J4-DETECTION_1-PadS1)") (class "Default")
      (node (ref "J4") (pin "S1") (pinfunction "DETECTION_1_S1") (pintype "bidirectional"))
    )
    (net (code "66") (name "unconnected-(J4-DETECTION_2-PadS2)") (class "Default")
      (node (ref "J4") (pin "S2") (pinfunction "DETECTION_2_S2") (pintype "bidirectional"))
    )
    (net (code "67") (name "unconnected-(U1-NC-Pad22)") (class "Default")
      (node (ref "U1") (pin "22") (pinfunction "NC_22") (pintype "no_connect"))
    )
    (net (code "68") (name "unconnected-(U4-~{ALERT}-Pad5)") (class "Default")
      (node (ref "U4") (pin "5") (pinfunction "~{ALERT}_5") (pintype "output"))
    )
  )
)
